# FMoto-Schematic.net
KiCad netlist of a schematic drawn in EAGLE
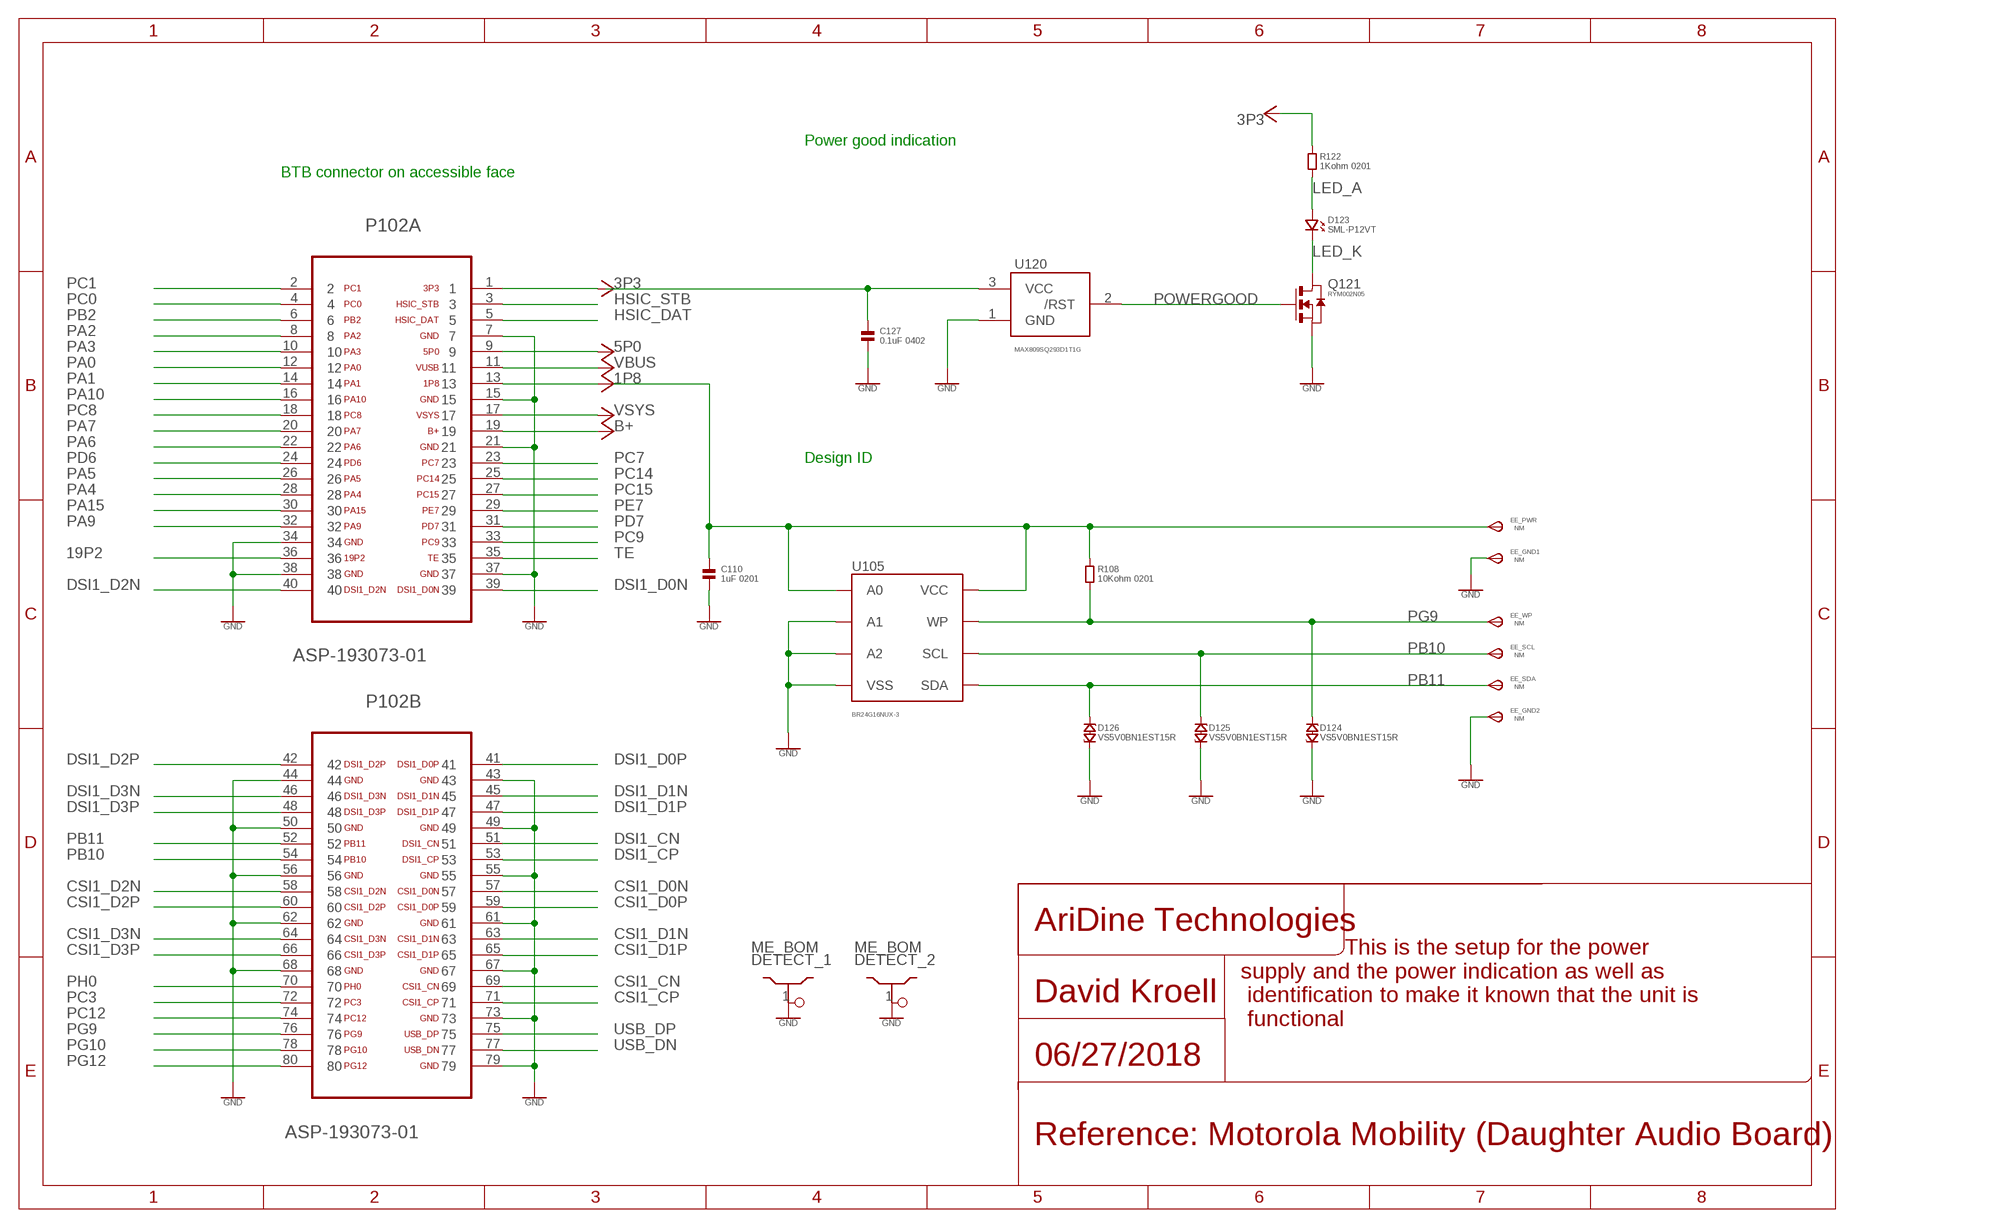
[diagram p0: schematic, sheet 1]
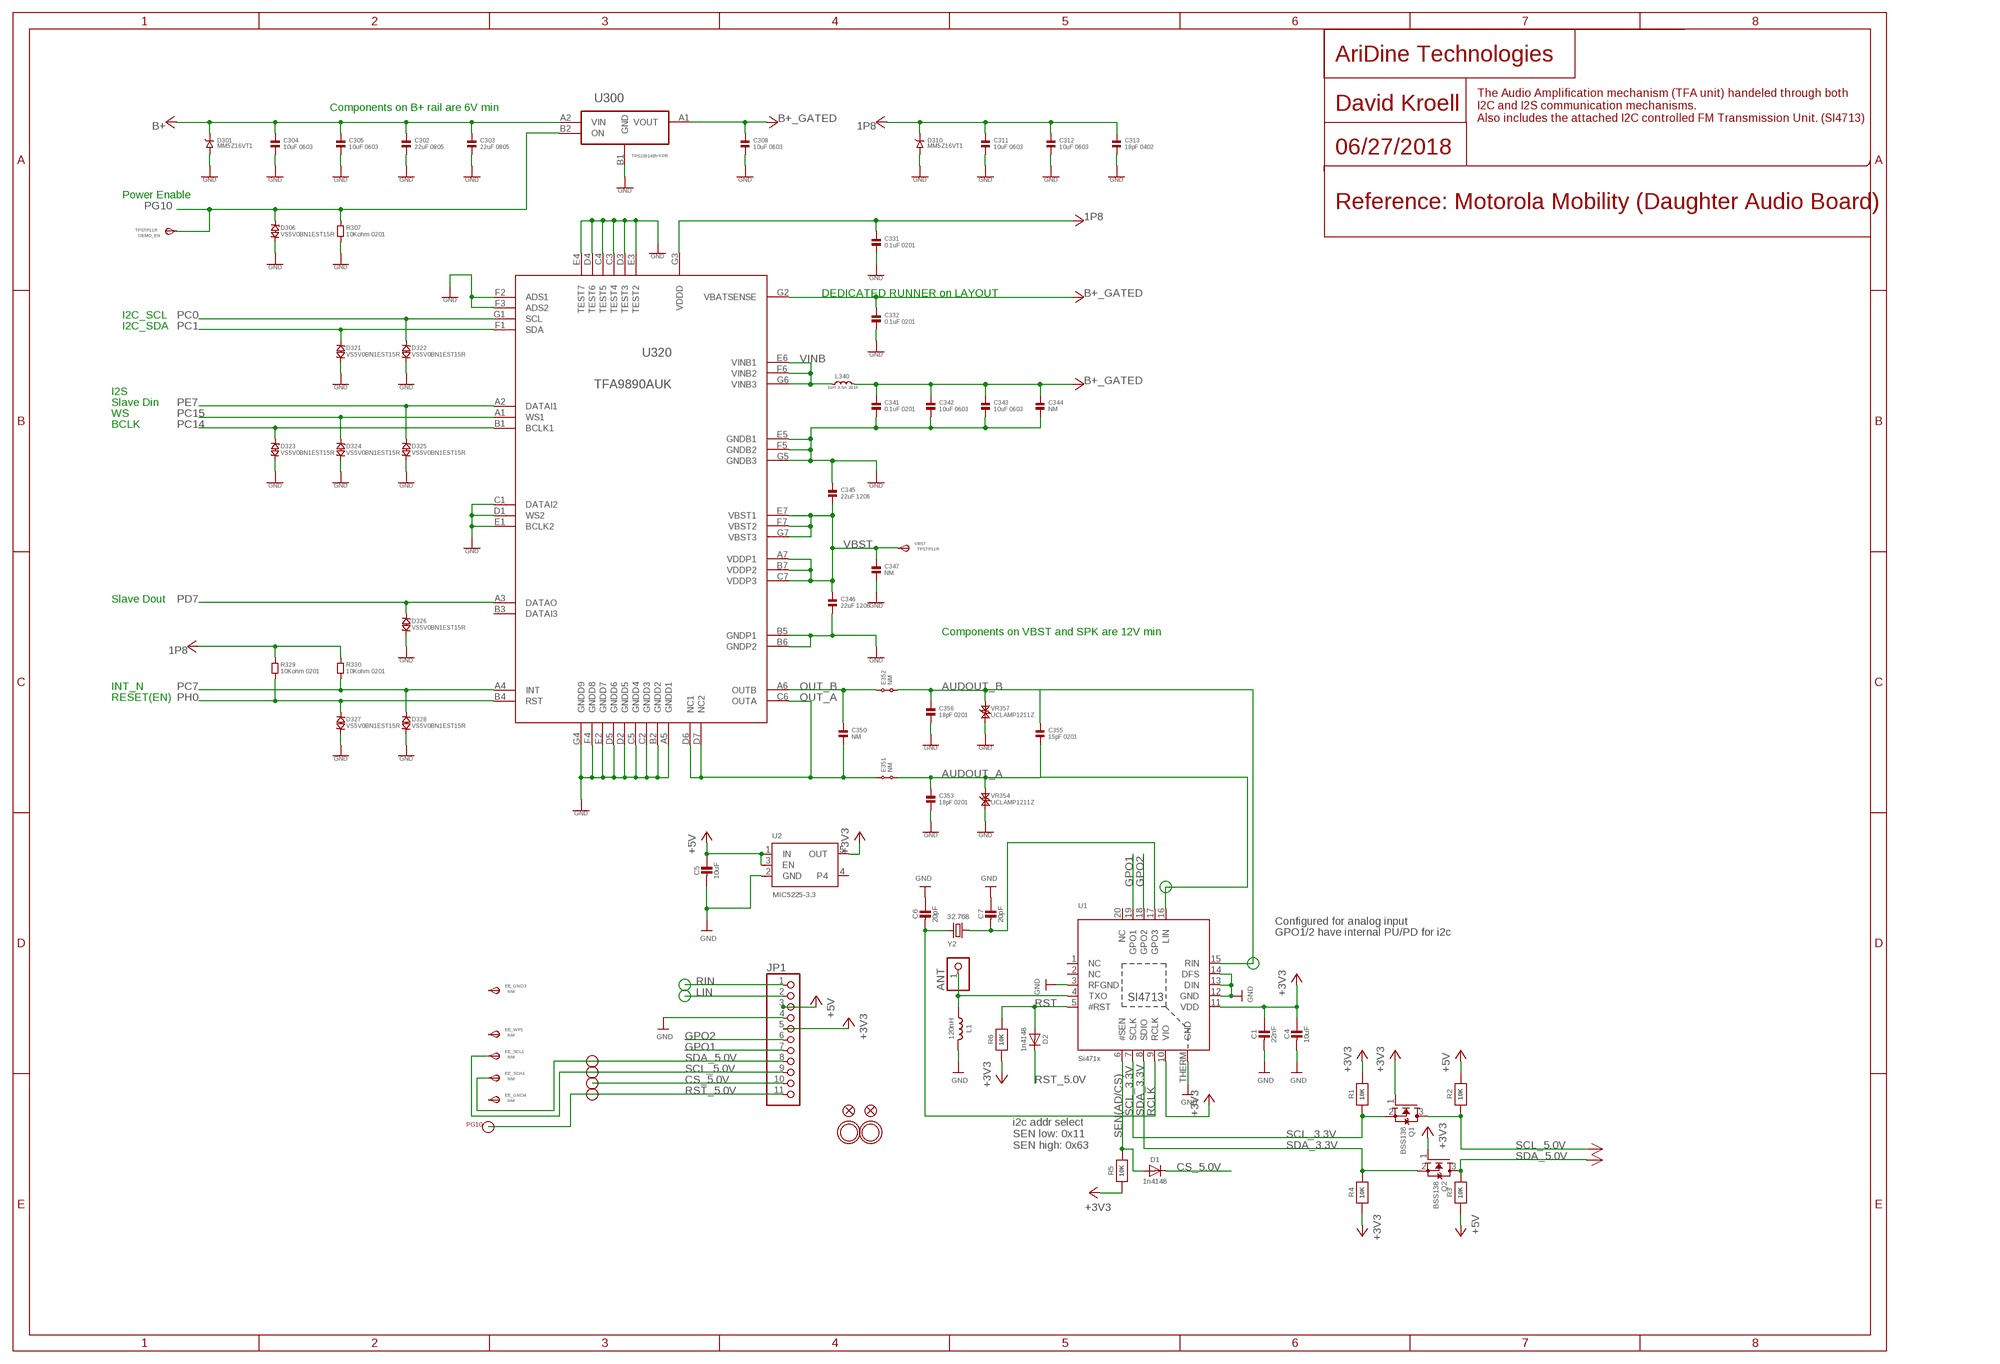
[diagram p1: schematic, sheet 2]

(export (version "E")
  (design (tool "Eeschema 10.0.6"))
  (components
    (comp (ref "ANT")
      (value "PINHD-1X1")
      (footprint "eagle-import:1X01")
      (libsource (lib "eagle-import") (part "PINHD-1X1"))
    )
    (comp (ref "C1")
      (value "22nF")
      (footprint "eagle-import:0805-NO")
      (libsource (lib "eagle-import") (part "CAP_CERAMIC0805-NOOUTLINE"))
    )
    (comp (ref "C4")
      (value "10uF")
      (footprint "eagle-import:0805-NO")
      (libsource (lib "eagle-import") (part "CAP_CERAMIC0805-NOOUTLINE"))
    )
    (comp (ref "C5")
      (value "10uF")
      (footprint "eagle-import:0805-NO")
      (libsource (lib "eagle-import") (part "CAP_CERAMIC0805-NOOUTLINE"))
    )
    (comp (ref "C6")
      (value "20pF")
      (footprint "eagle-import:0805-NO")
      (libsource (lib "eagle-import") (part "CAP_CERAMIC0805-NOOUTLINE"))
    )
    (comp (ref "C7")
      (value "20pF")
      (footprint "eagle-import:0805-NO")
      (libsource (lib "eagle-import") (part "CAP_CERAMIC0805-NOOUTLINE"))
    )
    (comp (ref "C302")
      (value "22uF 0805")
      (footprint "eagle-import:0805")
      (libsource (lib "eagle-import") (part "CAPACITOR.0805"))
    )
    (comp (ref "C303")
      (value "22uF 0805")
      (footprint "eagle-import:0805")
      (libsource (lib "eagle-import") (part "CAPACITOR.0805"))
    )
    (comp (ref "C304")
      (value "10uF 0603")
      (footprint "eagle-import:0603")
      (libsource (lib "eagle-import") (part "CAPACITOR.0603"))
    )
    (comp (ref "C305")
      (value "10uF 0603")
      (footprint "eagle-import:0603")
      (libsource (lib "eagle-import") (part "CAPACITOR.0603"))
    )
    (comp (ref "C308")
      (value "10uF 0603")
      (footprint "eagle-import:0603")
      (libsource (lib "eagle-import") (part "CAPACITOR.0603"))
    )
    (comp (ref "C311")
      (value "10uF 0603")
      (footprint "eagle-import:0603")
      (libsource (lib "eagle-import") (part "CAPACITOR.0603"))
    )
    (comp (ref "C312")
      (value "10uF 0603")
      (footprint "eagle-import:0603")
      (libsource (lib "eagle-import") (part "CAPACITOR.0603"))
    )
    (comp (ref "C313")
      (value "18pF 0402")
      (footprint "eagle-import:0402")
      (libsource (lib "eagle-import") (part "CAPACITOR.0402"))
    )
    (comp (ref "C331")
      (value "0.1uF 0201")
      (footprint "eagle-import:0201")
      (libsource (lib "eagle-import") (part "CAPACITOR.0201"))
    )
    (comp (ref "C332")
      (value "0.1uF 0201")
      (footprint "eagle-import:0201")
      (libsource (lib "eagle-import") (part "CAPACITOR.0201"))
    )
    (comp (ref "C341")
      (value "0.1uF 0201")
      (footprint "eagle-import:0201")
      (libsource (lib "eagle-import") (part "CAPACITOR.0201"))
    )
    (comp (ref "C342")
      (value "10uF 0603")
      (footprint "eagle-import:0603")
      (libsource (lib "eagle-import") (part "CAPACITOR.0603"))
    )
    (comp (ref "C343")
      (value "10uF 0603")
      (footprint "eagle-import:0603")
      (libsource (lib "eagle-import") (part "CAPACITOR.0603"))
    )
    (comp (ref "C344")
      (value "NM")
      (footprint "eagle-import:0402")
      (libsource (lib "eagle-import") (part "CAPACITOR.0402"))
    )
    (comp (ref "C345")
      (value "22uF 1206")
      (footprint "eagle-import:1206")
      (libsource (lib "eagle-import") (part "CAPACITOR.1206"))
    )
    (comp (ref "C346")
      (value "22uF 1206")
      (footprint "eagle-import:1206")
      (libsource (lib "eagle-import") (part "CAPACITOR.1206"))
    )
    (comp (ref "C347")
      (value "NM")
      (footprint "eagle-import:0402")
      (libsource (lib "eagle-import") (part "CAPACITOR.0402"))
    )
    (comp (ref "C350")
      (value "NM")
      (footprint "eagle-import:0201")
      (libsource (lib "eagle-import") (part "CAPACITOR.0201"))
    )
    (comp (ref "C353")
      (value "18pF 0201")
      (footprint "eagle-import:0201")
      (libsource (lib "eagle-import") (part "CAPACITOR.0201"))
    )
    (comp (ref "C355")
      (value "15pF 0201")
      (footprint "eagle-import:0201")
      (libsource (lib "eagle-import") (part "CAPACITOR.0201"))
    )
    (comp (ref "C356")
      (value "18pF 0201")
      (footprint "eagle-import:0201")
      (libsource (lib "eagle-import") (part "CAPACITOR.0201"))
    )
    (comp (ref "D1")
      (value "1n4148")
      (footprint "eagle-import:SOD-323")
      (libsource (lib "eagle-import") (part "DIODESOD-323"))
    )
    (comp (ref "D2")
      (value "1n4148")
      (footprint "eagle-import:SOD-323")
      (libsource (lib "eagle-import") (part "DIODESOD-323"))
    )
    (comp (ref "D301")
      (value "MM5Z16VT1")
      (footprint "eagle-import:SOD523")
      (libsource (lib "eagle-import") (part "DIODE.SOD523"))
    )
    (comp (ref "D306")
      (value "VS5V0BN1EST15R")
      (footprint "eagle-import:CHIP_0201")
      (libsource (lib "eagle-import") (part "ESD_VARISTOR.0201"))
    )
    (comp (ref "D310")
      (value "MM5Z16VT1")
      (footprint "eagle-import:SOD523")
      (libsource (lib "eagle-import") (part "DIODE.SOD523"))
    )
    (comp (ref "D321")
      (value "VS5V0BN1EST15R")
      (footprint "eagle-import:CHIP_0201")
      (libsource (lib "eagle-import") (part "ESD_VARISTOR.0201"))
    )
    (comp (ref "D322")
      (value "VS5V0BN1EST15R")
      (footprint "eagle-import:CHIP_0201")
      (libsource (lib "eagle-import") (part "ESD_VARISTOR.0201"))
    )
    (comp (ref "D323")
      (value "VS5V0BN1EST15R")
      (footprint "eagle-import:CHIP_0201")
      (libsource (lib "eagle-import") (part "ESD_VARISTOR.0201"))
    )
    (comp (ref "D324")
      (value "VS5V0BN1EST15R")
      (footprint "eagle-import:CHIP_0201")
      (libsource (lib "eagle-import") (part "ESD_VARISTOR.0201"))
    )
    (comp (ref "D325")
      (value "VS5V0BN1EST15R")
      (footprint "eagle-import:CHIP_0201")
      (libsource (lib "eagle-import") (part "ESD_VARISTOR.0201"))
    )
    (comp (ref "D326")
      (value "VS5V0BN1EST15R")
      (footprint "eagle-import:CHIP_0201")
      (libsource (lib "eagle-import") (part "ESD_VARISTOR.0201"))
    )
    (comp (ref "D327")
      (value "VS5V0BN1EST15R")
      (footprint "eagle-import:CHIP_0201")
      (libsource (lib "eagle-import") (part "ESD_VARISTOR.0201"))
    )
    (comp (ref "D328")
      (value "VS5V0BN1EST15R")
      (footprint "eagle-import:CHIP_0201")
      (libsource (lib "eagle-import") (part "ESD_VARISTOR.0201"))
    )
    (comp (ref "DEMO_EN")
      (value "TPSTP11R")
      (footprint "eagle-import:TP11R")
      (libsource (lib "eagle-import") (part "TPSTP11R"))
    )
    (comp (ref "E351")
      (value "NM")
      (footprint "eagle-import:0603_SHORT")
      (libsource (lib "eagle-import") (part "SHORT_BAR.0603"))
    )
    (comp (ref "E352")
      (value "NM")
      (footprint "eagle-import:0603_SHORT")
      (libsource (lib "eagle-import") (part "SHORT_BAR.0603"))
    )
    (comp (ref "EE_GND3")
      (value "NM")
      (footprint "eagle-import:TP11R")
      (libsource (lib "eagle-import") (part "TPSTP11R"))
    )
    (comp (ref "EE_GND4")
      (value "NM")
      (footprint "eagle-import:TP11R")
      (libsource (lib "eagle-import") (part "TPSTP11R"))
    )
    (comp (ref "EE_SCL1")
      (value "NM")
      (footprint "eagle-import:TP11R")
      (libsource (lib "eagle-import") (part "TPSTP11R"))
    )
    (comp (ref "EE_SDA1")
      (value "NM")
      (footprint "eagle-import:TP11R")
      (libsource (lib "eagle-import") (part "TPSTP11R"))
    )
    (comp (ref "EE_WP1")
      (value "NM")
      (footprint "eagle-import:TP11R")
      (libsource (lib "eagle-import") (part "TPSTP11R"))
    )
    (comp (ref "FID1")
      (value "FIDUCIAL\"\"")
      (footprint "eagle-import:FIDUCIAL_1MM")
      (libsource (lib "eagle-import") (part "FIDUCIAL{dblquote}{dblquote}"))
    )
    (comp (ref "FID2")
      (value "FIDUCIAL\"\"")
      (footprint "eagle-import:FIDUCIAL_1MM")
      (libsource (lib "eagle-import") (part "FIDUCIAL{dblquote}{dblquote}"))
    )
    (comp (ref "JP1")
      (value "HEADER-1X11")
      (footprint "eagle-import:1X11_ROUND")
      (libsource (lib "eagle-import") (part "HEADER-1X11"))
    )
    (comp (ref "L1")
      (value "120nH")
      (footprint "eagle-import:_0805")
      (libsource (lib "eagle-import") (part "INDUCTOR_0805"))
    )
    (comp (ref "L340")
      (value "1uH 3.5A 2016")
      (footprint "eagle-import:2016")
      (libsource (lib "eagle-import") (part "POWER-INDUCTOR.2016"))
    )
    (comp (ref "Q1")
      (value "BSS138")
      (footprint "eagle-import:SOT23")
      (libsource (lib "eagle-import") (part "MOSFET-NREFLOW"))
    )
    (comp (ref "Q2")
      (value "BSS138")
      (footprint "eagle-import:SOT23")
      (libsource (lib "eagle-import") (part "MOSFET-NREFLOW"))
    )
    (comp (ref "R1")
      (value "10K")
      (footprint "eagle-import:0805-NO")
      (libsource (lib "eagle-import") (part "RESISTOR0805_NOOUTLINE"))
    )
    (comp (ref "R2")
      (value "10K")
      (footprint "eagle-import:_0805MP")
      (libsource (lib "eagle-import") (part "RESISTOR_0805MP"))
    )
    (comp (ref "R3")
      (value "10K")
      (footprint "eagle-import:0805-NO")
      (libsource (lib "eagle-import") (part "RESISTOR0805_NOOUTLINE"))
    )
    (comp (ref "R4")
      (value "10K")
      (footprint "eagle-import:_0805MP")
      (libsource (lib "eagle-import") (part "RESISTOR_0805MP"))
    )
    (comp (ref "R5")
      (value "10K")
      (footprint "eagle-import:0805-NO")
      (libsource (lib "eagle-import") (part "RESISTOR0805_NOOUTLINE"))
    )
    (comp (ref "R6")
      (value "10K")
      (footprint "eagle-import:0805-NO")
      (libsource (lib "eagle-import") (part "RESISTOR0805_NOOUTLINE"))
    )
    (comp (ref "R307")
      (value "10Kohm 0201")
      (footprint "eagle-import:0201")
      (libsource (lib "eagle-import") (part "RESISTOR.0201"))
    )
    (comp (ref "R329")
      (value "10Kohm 0201")
      (footprint "eagle-import:0201")
      (libsource (lib "eagle-import") (part "RESISTOR.0201"))
    )
    (comp (ref "R330")
      (value "10Kohm 0201")
      (footprint "eagle-import:0201")
      (libsource (lib "eagle-import") (part "RESISTOR.0201"))
    )
    (comp (ref "U$15")
      (value "MOUNTINGHOLE2.5")
      (footprint "eagle-import:MOUNTINGHOLE_2.5_PLATED")
      (libsource (lib "eagle-import") (part "MOUNTINGHOLE2.5"))
    )
    (comp (ref "U$17")
      (value "MOUNTINGHOLE2.5")
      (footprint "eagle-import:MOUNTINGHOLE_2.5_PLATED")
      (libsource (lib "eagle-import") (part "MOUNTINGHOLE2.5"))
    )
    (comp (ref "U1")
      (value "Si471x")
      (footprint "eagle-import:SI471X")
      (libsource (lib "eagle-import") (part "SI471X"))
    )
    (comp (ref "U2")
      (value "MIC5225-3.3")
      (footprint "eagle-import:SOT23-5")
      (libsource (lib "eagle-import") (part "VREG_SOT23-5"))
    )
    (comp (ref "U300")
      (value "TPS22914BYFPR")
      (footprint "eagle-import:BGA0_75SQ_PS0_4_P4")
      (libsource (lib "eagle-import") (part "TPS22914BYFPR"))
    )
    (comp (ref "U320")
      (value "TFA9890AUK")
      (footprint "eagle-import:BGA7X7")
      (libsource (lib "eagle-import") (part "TFA9890AUK"))
    )
    (comp (ref "VBST")
      (value "TPSTP11R")
      (footprint "eagle-import:TP11R")
      (libsource (lib "eagle-import") (part "TPSTP11R"))
    )
    (comp (ref "VR354")
      (value "UCLAMP1211Z")
      (footprint "eagle-import:CHIP_0201")
      (libsource (lib "eagle-import") (part "ESD_TVS.0201"))
    )
    (comp (ref "VR357")
      (value "UCLAMP1211Z")
      (footprint "eagle-import:CHIP_0201")
      (libsource (lib "eagle-import") (part "ESD_TVS.0201"))
    )
    (comp (ref "Y2")
      (value "32.768")
      (footprint "eagle-import:CRYSTAL_8X3.8")
      (libsource (lib "eagle-import") (part "CRYSTAL8.0X3.8"))
    )
    (comp (ref "C110")
      (value "1uF 0201")
      (footprint "eagle-import:0201")
      (libsource (lib "eagle-import") (part "CAPACITOR.0201"))
    )
    (comp (ref "C127")
      (value "0.1uF 0402")
      (footprint "eagle-import:0402")
      (libsource (lib "eagle-import") (part "CAPACITOR.0402"))
    )
    (comp (ref "D123")
      (value "SML-P12VT")
      (footprint "eagle-import:0503.LED")
      (libsource (lib "eagle-import") (part "LED.0503"))
    )
    (comp (ref "D124")
      (value "VS5V0BN1EST15R")
      (footprint "eagle-import:CHIP_0201")
      (libsource (lib "eagle-import") (part "ESD_VARISTOR.0201"))
    )
    (comp (ref "D125")
      (value "VS5V0BN1EST15R")
      (footprint "eagle-import:CHIP_0201")
      (libsource (lib "eagle-import") (part "ESD_VARISTOR.0201"))
    )
    (comp (ref "D126")
      (value "VS5V0BN1EST15R")
      (footprint "eagle-import:CHIP_0201")
      (libsource (lib "eagle-import") (part "ESD_VARISTOR.0201"))
    )
    (comp (ref "DETECT_1")
      (value "ME_BOM")
      (footprint "eagle-import:PLUG")
      (fields (field (name "MPN") "refer to ME BOM"))
      (libsource (lib "eagle-import") (part "SHIELDDETECT"))
    )
    (comp (ref "DETECT_2")
      (value "ME_BOM")
      (footprint "eagle-import:PLUG")
      (fields (field (name "MPN") "refer to ME BOM"))
      (libsource (lib "eagle-import") (part "SHIELDDETECT"))
    )
    (comp (ref "EE_GND1")
      (value "NM")
      (footprint "eagle-import:TP11R")
      (libsource (lib "eagle-import") (part "TPSTP11R"))
    )
    (comp (ref "EE_GND2")
      (value "NM")
      (footprint "eagle-import:TP11R")
      (libsource (lib "eagle-import") (part "TPSTP11R"))
    )
    (comp (ref "EE_PWR")
      (value "NM")
      (footprint "eagle-import:TP11R")
      (libsource (lib "eagle-import") (part "TPSTP11R"))
    )
    (comp (ref "EE_SCL")
      (value "NM")
      (footprint "eagle-import:TP11R")
      (libsource (lib "eagle-import") (part "TPSTP11R"))
    )
    (comp (ref "EE_SDA")
      (value "NM")
      (footprint "eagle-import:TP11R")
      (libsource (lib "eagle-import") (part "TPSTP11R"))
    )
    (comp (ref "EE_WP")
      (value "NM")
      (footprint "eagle-import:TP11R")
      (libsource (lib "eagle-import") (part "TPSTP11R"))
    )
    (comp (ref "P102")
      (value "ASP-193073-01")
      (footprint "eagle-import:FTMH-140-02-L-DV-ES-P-TR")
      (fields (field (name "MPN") "ASP-193073-01"))
      (libsource (lib "eagle-import") (part "FTMH-140-02-L-DV-ES-P-TR"))
    )
    (comp (ref "Q121")
      (value "RYM002N05")
      (footprint "eagle-import:VMT3")
      (libsource (lib "eagle-import") (part "FET-NRYM002N05"))
    )
    (comp (ref "R108")
      (value "10Kohm 0201")
      (footprint "eagle-import:0201")
      (libsource (lib "eagle-import") (part "RESISTOR.0201"))
    )
    (comp (ref "R122")
      (value "1Kohm 0201")
      (footprint "eagle-import:0201")
      (libsource (lib "eagle-import") (part "RESISTOR.0201"))
    )
    (comp (ref "U105")
      (value "BR24G16NUX-3")
      (footprint "eagle-import:DFN-8")
      (libsource (lib "eagle-import") (part "EEPROMDFN8"))
    )
    (comp (ref "U120")
      (value "MAX809SQ293D1T1G")
      (footprint "eagle-import:SC70-3L")
      (fields (field (name "MPN") "MAX809SQ293D1T1"))
      (libsource (lib "eagle-import") (part "MAX809"))
    )
  )
  (nets
    (net (code "1") (name "+3V3") (class "Default")
      (node (ref "C1") (pin "1") (pinfunction "1_1") (pintype "passive"))
      (node (ref "C4") (pin "1") (pinfunction "1_1") (pintype "passive"))
      (node (ref "JP1") (pin "5") (pinfunction "5_5") (pintype "passive"))
      (node (ref "Q1") (pin "1") (pinfunction "G_1") (pintype "bidirectional"))
      (node (ref "Q2") (pin "1") (pinfunction "G_1") (pintype "bidirectional"))
      (node (ref "R1") (pin "2") (pinfunction "2_2") (pintype "passive"))
      (node (ref "R4") (pin "1") (pinfunction "1_1") (pintype "passive"))
      (node (ref "R5") (pin "1") (pinfunction "1_1") (pintype "passive"))
      (node (ref "R6") (pin "1") (pinfunction "1_1") (pintype "passive"))
      (node (ref "U1") (pin "10") (pinfunction "VIO_10") (pintype "bidirectional"))
      (node (ref "U1") (pin "11") (pinfunction "VDD_11") (pintype "bidirectional"))
      (node (ref "U2") (pin "5") (pinfunction "OUT_5") (pintype "power_in"))
    )
    (net (code "2") (name "+5V") (class "Default")
      (node (ref "C5") (pin "1") (pinfunction "1_1") (pintype "passive"))
      (node (ref "JP1") (pin "3") (pinfunction "3_3") (pintype "passive"))
      (node (ref "R2") (pin "2") (pinfunction "2_2") (pintype "passive"))
      (node (ref "R3") (pin "1") (pinfunction "1_1") (pintype "passive"))
      (node (ref "U2") (pin "1") (pinfunction "IN_1") (pintype "power_in"))
      (node (ref "U2") (pin "3") (pinfunction "EN_3") (pintype "input"))
    )
    (net (code "3") (name "1P8") (class "Default")
      (node (ref "C311") (pin "1") (pinfunction "1_1") (pintype "bidirectional"))
      (node (ref "C312") (pin "1") (pinfunction "1_1") (pintype "bidirectional"))
      (node (ref "C313") (pin "1") (pinfunction "1_1") (pintype "bidirectional"))
      (node (ref "C331") (pin "1") (pinfunction "1_1") (pintype "bidirectional"))
      (node (ref "D310") (pin "1") (pinfunction "1_1") (pintype "bidirectional"))
      (node (ref "P102") (pin "13") (pinfunction "13_13") (pintype "passive"))
      (node (ref "R329") (pin "1") (pinfunction "1_1") (pintype "bidirectional"))
      (node (ref "R330") (pin "1") (pinfunction "1_1") (pintype "bidirectional"))
      (node (ref "U320") (pin "G3") (pinfunction "VDDD_G3") (pintype "bidirectional"))
    )
    (net (code "4") (name "3P3") (class "Default")
      (node (ref "P102") (pin "1") (pinfunction "1_1") (pintype "passive"))
      (node (ref "R122") (pin "1") (pinfunction "1_1") (pintype "bidirectional"))
    )
    (net (code "5") (name "5P0") (class "Default")
      (node (ref "P102") (pin "9") (pinfunction "9_9") (pintype "passive"))
    )
    (net (code "6") (name "19P2") (class "Default")
      (node (ref "P102") (pin "36") (pinfunction "36_36") (pintype "passive"))
    )
    (net (code "7") (name "AUDOUT_A") (class "Default")
      (node (ref "C353") (pin "1") (pinfunction "1_1") (pintype "bidirectional"))
      (node (ref "C355") (pin "2") (pinfunction "2_2") (pintype "bidirectional"))
      (node (ref "E351") (pin "2") (pinfunction "2_2") (pintype "bidirectional"))
      (node (ref "U1") (pin "16") (pinfunction "LIN_16") (pintype "bidirectional"))
      (node (ref "VR354") (pin "P$1") (pinfunction "1_P$1") (pintype "bidirectional"))
    )
    (net (code "8") (name "AUDOUT_B") (class "Default")
      (node (ref "C355") (pin "1") (pinfunction "1_1") (pintype "bidirectional"))
      (node (ref "C356") (pin "1") (pinfunction "1_1") (pintype "bidirectional"))
      (node (ref "E352") (pin "2") (pinfunction "2_2") (pintype "bidirectional"))
      (node (ref "U1") (pin "15") (pinfunction "RIN_15") (pintype "bidirectional"))
      (node (ref "VR357") (pin "P$1") (pinfunction "1_P$1") (pintype "bidirectional"))
    )
    (net (code "9") (name "B+") (class "Default")
      (node (ref "C302") (pin "1") (pinfunction "1_1") (pintype "bidirectional"))
      (node (ref "C303") (pin "1") (pinfunction "1_1") (pintype "bidirectional"))
      (node (ref "C304") (pin "1") (pinfunction "1_1") (pintype "bidirectional"))
      (node (ref "C305") (pin "1") (pinfunction "1_1") (pintype "bidirectional"))
      (node (ref "D301") (pin "1") (pinfunction "1_1") (pintype "bidirectional"))
      (node (ref "P102") (pin "19") (pinfunction "19_19") (pintype "passive"))
      (node (ref "U300") (pin "A2") (pinfunction "VIN_A2") (pintype "power_in"))
    )
    (net (code "10") (name "B+_GATED") (class "Default")
      (node (ref "C308") (pin "1") (pinfunction "1_1") (pintype "bidirectional"))
      (node (ref "C332") (pin "1") (pinfunction "1_1") (pintype "bidirectional"))
      (node (ref "C341") (pin "1") (pinfunction "1_1") (pintype "bidirectional"))
      (node (ref "C342") (pin "1") (pinfunction "1_1") (pintype "bidirectional"))
      (node (ref "C343") (pin "1") (pinfunction "1_1") (pintype "bidirectional"))
      (node (ref "C344") (pin "1") (pinfunction "1_1") (pintype "bidirectional"))
      (node (ref "L340") (pin "2") (pinfunction "2_2") (pintype "passive"))
      (node (ref "U300") (pin "A1") (pinfunction "VOUT_A1") (pintype "power_in"))
      (node (ref "U320") (pin "G2") (pinfunction "VBATSENSE_G2") (pintype "bidirectional"))
    )
    (net (code "11") (name "CSI1_CN") (class "Default")
      (node (ref "P102") (pin "69") (pinfunction "69_69") (pintype "passive"))
    )
    (net (code "12") (name "CSI1_CP") (class "Default")
      (node (ref "P102") (pin "71") (pinfunction "71_71") (pintype "passive"))
    )
    (net (code "13") (name "CSI1_D0N") (class "Default")
      (node (ref "P102") (pin "57") (pinfunction "57_57") (pintype "passive"))
    )
    (net (code "14") (name "CSI1_D0P") (class "Default")
      (node (ref "P102") (pin "59") (pinfunction "59_59") (pintype "passive"))
    )
    (net (code "15") (name "CSI1_D1N") (class "Default")
      (node (ref "P102") (pin "63") (pinfunction "63_63") (pintype "passive"))
    )
    (net (code "16") (name "CSI1_D1P") (class "Default")
      (node (ref "P102") (pin "65") (pinfunction "65_65") (pintype "passive"))
    )
    (net (code "17") (name "CSI1_D2N") (class "Default")
      (node (ref "P102") (pin "58") (pinfunction "58_58") (pintype "passive"))
    )
    (net (code "18") (name "CSI1_D2P") (class "Default")
      (node (ref "P102") (pin "60") (pinfunction "60_60") (pintype "passive"))
    )
    (net (code "19") (name "CSI1_D3N") (class "Default")
      (node (ref "P102") (pin "64") (pinfunction "64_64") (pintype "passive"))
    )
    (net (code "20") (name "CSI1_D3P") (class "Default")
      (node (ref "P102") (pin "66") (pinfunction "66_66") (pintype "passive"))
    )
    (net (code "21") (name "CS_5.0V") (class "Default")
      (node (ref "D1") (pin "C") (pinfunction "C_C") (pintype "passive"))
      (node (ref "JP1") (pin "10") (pinfunction "10_10") (pintype "passive"))
    )
    (net (code "22") (name "DSI1_CN") (class "Default")
      (node (ref "P102") (pin "51") (pinfunction "51_51") (pintype "passive"))
    )
    (net (code "23") (name "DSI1_CP") (class "Default")
      (node (ref "P102") (pin "53") (pinfunction "53_53") (pintype "passive"))
    )
    (net (code "24") (name "DSI1_D0N") (class "Default")
      (node (ref "P102") (pin "39") (pinfunction "39_39") (pintype "passive"))
    )
    (net (code "25") (name "DSI1_D0P") (class "Default")
      (node (ref "P102") (pin "41") (pinfunction "41_41") (pintype "passive"))
    )
    (net (code "26") (name "DSI1_D1N") (class "Default")
      (node (ref "P102") (pin "45") (pinfunction "45_45") (pintype "passive"))
    )
    (net (code "27") (name "DSI1_D1P") (class "Default")
      (node (ref "P102") (pin "47") (pinfunction "47_47") (pintype "passive"))
    )
    (net (code "28") (name "DSI1_D2N") (class "Default")
      (node (ref "P102") (pin "40") (pinfunction "40_40") (pintype "passive"))
    )
    (net (code "29") (name "DSI1_D2P") (class "Default")
      (node (ref "P102") (pin "42") (pinfunction "42_42") (pintype "passive"))
    )
    (net (code "30") (name "DSI1_D3N") (class "Default")
      (node (ref "P102") (pin "46") (pinfunction "46_46") (pintype "passive"))
    )
    (net (code "31") (name "DSI1_D3P") (class "Default")
      (node (ref "P102") (pin "48") (pinfunction "48_48") (pintype "passive"))
    )
    (net (code "32") (name "GND") (class "Default")
      (node (ref "C1") (pin "2") (pinfunction "2_2") (pintype "passive"))
      (node (ref "C110") (pin "2") (pinfunction "2_2") (pintype "bidirectional"))
      (node (ref "C127") (pin "2") (pinfunction "2_2") (pintype "bidirectional"))
      (node (ref "C302") (pin "2") (pinfunction "2_2") (pintype "bidirectional"))
      (node (ref "C303") (pin "2") (pinfunction "2_2") (pintype "bidirectional"))
      (node (ref "C304") (pin "2") (pinfunction "2_2") (pintype "bidirectional"))
      (node (ref "C305") (pin "2") (pinfunction "2_2") (pintype "bidirectional"))
      (node (ref "C308") (pin "2") (pinfunction "2_2") (pintype "bidirectional"))
      (node (ref "C311") (pin "2") (pinfunction "2_2") (pintype "bidirectional"))
      (node (ref "C312") (pin "2") (pinfunction "2_2") (pintype "bidirectional"))
      (node (ref "C313") (pin "2") (pinfunction "2_2") (pintype "bidirectional"))
      (node (ref "C331") (pin "2") (pinfunction "2_2") (pintype "bidirectional"))
      (node (ref "C332") (pin "2") (pinfunction "2_2") (pintype "bidirectional"))
      (node (ref "C341") (pin "2") (pinfunction "2_2") (pintype "bidirectional"))
      (node (ref "C342") (pin "2") (pinfunction "2_2") (pintype "bidirectional"))
      (node (ref "C343") (pin "2") (pinfunction "2_2") (pintype "bidirectional"))
      (node (ref "C344") (pin "2") (pinfunction "2_2") (pintype "bidirectional"))
      (node (ref "C345") (pin "1") (pinfunction "1_1") (pintype "bidirectional"))
      (node (ref "C346") (pin "2") (pinfunction "2_2") (pintype "bidirectional"))
      (node (ref "C347") (pin "2") (pinfunction "2_2") (pintype "bidirectional"))
      (node (ref "C353") (pin "2") (pinfunction "2_2") (pintype "bidirectional"))
      (node (ref "C356") (pin "2") (pinfunction "2_2") (pintype "bidirectional"))
      (node (ref "C4") (pin "2") (pinfunction "2_2") (pintype "passive"))
      (node (ref "C5") (pin "2") (pinfunction "2_2") (pintype "passive"))
      (node (ref "C6") (pin "1") (pinfunction "1_1") (pintype "passive"))
      (node (ref "C7") (pin "1") (pinfunction "1_1") (pintype "passive"))
      (node (ref "D124") (pin "P$2") (pinfunction "2_P$2") (pintype "bidirectional"))
      (node (ref "D125") (pin "P$2") (pinfunction "2_P$2") (pintype "bidirectional"))
      (node (ref "D126") (pin "P$2") (pinfunction "2_P$2") (pintype "bidirectional"))
      (node (ref "D301") (pin "2") (pinfunction "2_2") (pintype "bidirectional"))
      (node (ref "D306") (pin "P$2") (pinfunction "2_P$2") (pintype "bidirectional"))
      (node (ref "D310") (pin "2") (pinfunction "2_2") (pintype "bidirectional"))
      (node (ref "D321") (pin "P$2") (pinfunction "2_P$2") (pintype "bidirectional"))
      (node (ref "D322") (pin "P$2") (pinfunction "2_P$2") (pintype "bidirectional"))
      (node (ref "D323") (pin "P$2") (pinfunction "2_P$2") (pintype "bidirectional"))
      (node (ref "D324") (pin "P$2") (pinfunction "2_P$2") (pintype "bidirectional"))
      (node (ref "D325") (pin "P$2") (pinfunction "2_P$2") (pintype "bidirectional"))
      (node (ref "D326") (pin "P$2") (pinfunction "2_P$2") (pintype "bidirectional"))
      (node (ref "D327") (pin "P$2") (pinfunction "2_P$2") (pintype "bidirectional"))
      (node (ref "D328") (pin "P$2") (pinfunction "2_P$2") (pintype "bidirectional"))
      (node (ref "DETECT_1") (pin "1") (pinfunction "1_1") (pintype "passive"))
      (node (ref "DETECT_2") (pin "1") (pinfunction "1_1") (pintype "passive"))
      (node (ref "EE_GND1") (pin "TP") (pinfunction "PP_TP") (pintype "input"))
      (node (ref "EE_GND2") (pin "TP") (pinfunction "PP_TP") (pintype "input"))
      (node (ref "JP1") (pin "4") (pinfunction "4_4") (pintype "passive"))
      (node (ref "L1") (pin "2") (pinfunction "2_2") (pintype "passive"))
      (node (ref "P102") (pin "15") (pinfunction "15_15") (pintype "passive"))
      (node (ref "P102") (pin "21") (pinfunction "21_21") (pintype "passive"))
      (node (ref "P102") (pin "34") (pinfunction "34_34") (pintype "passive"))
      (node (ref "P102") (pin "37") (pinfunction "37_37") (pintype "passive"))
      (node (ref "P102") (pin "38") (pinfunction "38_38") (pintype "passive"))
      (node (ref "P102") (pin "43") (pinfunction "43_43") (pintype "passive"))
      (node (ref "P102") (pin "44") (pinfunction "44_44") (pintype "passive"))
      (node (ref "P102") (pin "49") (pinfunction "49_49") (pintype "passive"))
      (node (ref "P102") (pin "50") (pinfunction "50_50") (pintype "passive"))
      (node (ref "P102") (pin "55") (pinfunction "55_55") (pintype "passive"))
      (node (ref "P102") (pin "56") (pinfunction "56_56") (pintype "passive"))
      (node (ref "P102") (pin "61") (pinfunction "61_61") (pintype "passive"))
      (node (ref "P102") (pin "62") (pinfunction "62_62") (pintype "passive"))
      (node (ref "P102") (pin "67") (pinfunction "67_67") (pintype "passive"))
      (node (ref "P102") (pin "68") (pinfunction "68_68") (pintype "passive"))
      (node (ref "P102") (pin "7") (pinfunction "7_7") (pintype "passive"))
      (node (ref "P102") (pin "73") (pinfunction "73_73") (pintype "passive"))
      (node (ref "P102") (pin "79") (pinfunction "79_79") (pintype "passive"))
      (node (ref "Q121") (pin "2") (pinfunction "S_2") (pintype "passive"))
      (node (ref "R307") (pin "2") (pinfunction "2_2") (pintype "bidirectional"))
      (node (ref "U1") (pin "12") (pinfunction "GND_12") (pintype "bidirectional"))
      (node (ref "U1") (pin "13") (pinfunction "DIN_13") (pintype "bidirectional"))
      (node (ref "U1") (pin "14") (pinfunction "DFS_14") (pintype "bidirectional"))
      (node (ref "U1") (pin "3") (pinfunction "RFGND_3") (pintype "bidirectional"))
      (node (ref "U1") (pin "THERM") (pinfunction "GND_THERM") (pintype "bidirectional"))
      (node (ref "U105") (pin "P$2") (pinfunction "A1_P$2") (pintype "input"))
      (node (ref "U105") (pin "P$3") (pinfunction "A2_P$3") (pintype "input"))
      (node (ref "U105") (pin "P$4") (pinfunction "VSS_P$4") (pintype "power_in"))
      (node (ref "U105") (pin "P$9") (pinfunction "VSS_P$9") (pintype "power_in"))
      (node (ref "U120") (pin "1") (pinfunction "GND_1") (pintype "power_in"))
      (node (ref "U2") (pin "2") (pinfunction "GND_2") (pintype "power_in"))
      (node (ref "U300") (pin "B1") (pinfunction "GND_B1") (pintype "power_in"))
      (node (ref "U320") (pin "A5") (pinfunction "GNDD1_A5") (pintype "bidirectional"))
      (node (ref "U320") (pin "B2") (pinfunction "GNDD2_B2") (pintype "bidirectional"))
      (node (ref "U320") (pin "B5") (pinfunction "GNDP1_B5") (pintype "bidirectional"))
      (node (ref "U320") (pin "B6") (pinfunction "GNDP2_B6") (pintype "bidirectional"))
      (node (ref "U320") (pin "C1") (pinfunction "DATAI2_C1") (pintype "bidirectional"))
      (node (ref "U320") (pin "C2") (pinfunction "GNDD3_C2") (pintype "bidirectional"))
      (node (ref "U320") (pin "C3") (pinfunction "TEST4_C3") (pintype "bidirectional"))
      (node (ref "U320") (pin "C4") (pinfunction "TEST5_C4") (pintype "bidirectional"))
      (node (ref "U320") (pin "C5") (pinfunction "GNDD4_C5") (pintype "bidirectional"))
      (node (ref "U320") (pin "D1") (pinfunction "WS2_D1") (pintype "bidirectional"))
      (node (ref "U320") (pin "D2") (pinfunction "GNDD5_D2") (pintype "bidirectional"))
      (node (ref "U320") (pin "D3") (pinfunction "TEST3_D3") (pintype "bidirectional"))
      (node (ref "U320") (pin "D4") (pinfunction "TEST6_D4") (pintype "bidirectional"))
      (node (ref "U320") (pin "D5") (pinfunction "GNDD6_D5") (pintype "bidirectional"))
      (node (ref "U320") (pin "E1") (pinfunction "BCLK2_E1") (pintype "bidirectional"))
      (node (ref "U320") (pin "E2") (pinfunction "GNDD7_E2") (pintype "bidirectional"))
      (node (ref "U320") (pin "E3") (pinfunction "TEST2_E3") (pintype "bidirectional"))
      (node (ref "U320") (pin "E4") (pinfunction "TEST7_E4") (pintype "bidirectional"))
      (node (ref "U320") (pin "E5") (pinfunction "GNDB1_E5") (pintype "bidirectional"))
      (node (ref "U320") (pin "F2") (pinfunction "ADS1_F2") (pintype "bidirectional"))
      (node (ref "U320") (pin "F3") (pinfunction "ADS2_F3") (pintype "bidirectional"))
      (node (ref "U320") (pin "F4") (pinfunction "GNDD8_F4") (pintype "bidirectional"))
      (node (ref "U320") (pin "F5") (pinfunction "GNDB2_F5") (pintype "bidirectional"))
      (node (ref "U320") (pin "G4") (pinfunction "GNDD9_G4") (pintype "bidirectional"))
      (node (ref "U320") (pin "G5") (pinfunction "GNDB3_G5") (pintype "bidirectional"))
      (node (ref "VR354") (pin "P$2") (pinfunction "2_P$2") (pintype "bidirectional"))
      (node (ref "VR357") (pin "P$2") (pinfunction "2_P$2") (pintype "bidirectional"))
    )
    (net (code "33") (name "GPO1") (class "Default")
      (node (ref "JP1") (pin "7") (pinfunction "7_7") (pintype "passive"))
      (node (ref "U1") (pin "19") (pinfunction "GPO1_19") (pintype "bidirectional"))
    )
    (net (code "34") (name "GPO2") (class "Default")
      (node (ref "JP1") (pin "6") (pinfunction "6_6") (pintype "passive"))
      (node (ref "U1") (pin "18") (pinfunction "GPO2_18") (pintype "bidirectional"))
    )
    (net (code "35") (name "HSIC_DAT") (class "Default")
      (node (ref "P102") (pin "5") (pinfunction "5_5") (pintype "passive"))
    )
    (net (code "36") (name "HSIC_STB") (class "Default")
      (node (ref "P102") (pin "3") (pinfunction "3_3") (pintype "passive"))
    )
    (net (code "37") (name "LED_A") (class "Default")
      (node (ref "D123") (pin "P$1") (pinfunction "1_P$1") (pintype "bidirectional"))
      (node (ref "R122") (pin "2") (pinfunction "2_2") (pintype "bidirectional"))
    )
    (net (code "38") (name "LED_K") (class "Default")
      (node (ref "D123") (pin "P$2") (pinfunction "2_P$2") (pintype "bidirectional"))
      (node (ref "Q121") (pin "3") (pinfunction "D_3") (pintype "passive"))
    )
    (net (code "39") (name "LIN") (class "Default")
      (node (ref "JP1") (pin "2") (pinfunction "2_2") (pintype "passive"))
    )
    (net (code "40") (name "Net-(EE_PWR-PP)") (class "Default")
      (node (ref "C110") (pin "1") (pinfunction "1_1") (pintype "bidirectional"))
      (node (ref "EE_PWR") (pin "TP") (pinfunction "PP_TP") (pintype "input"))
      (node (ref "R108") (pin "1") (pinfunction "1_1") (pintype "bidirectional"))
      (node (ref "U105") (pin "P$1") (pinfunction "A0_P$1") (pintype "input"))
      (node (ref "U105") (pin "P$8") (pinfunction "VCC_P$8") (pintype "power_in"))
    )
    (net (code "41") (name "Net-(U1-GPO3)") (class "Default")
      (node (ref "C7") (pin "2") (pinfunction "2_2") (pintype "passive"))
      (node (ref "U1") (pin "17") (pinfunction "GPO3_17") (pintype "bidirectional"))
      (node (ref "Y2") (pin "P$4") (pinfunction "2_P$4") (pintype "passive"))
    )
    (net (code "42") (name "Net-(U1-TXO)") (class "Default")
      (node (ref "ANT") (pin "1") (pinfunction "1_1") (pintype "passive"))
      (node (ref "L1") (pin "1") (pinfunction "1_1") (pintype "passive"))
      (node (ref "U1") (pin "4") (pinfunction "TXO_4") (pintype "bidirectional"))
    )
    (net (code "43") (name "Net-(U120-VCC)") (class "Default")
      (node (ref "C127") (pin "1") (pinfunction "1_1") (pintype "bidirectional"))
      (node (ref "U120") (pin "3") (pinfunction "VCC_3") (pintype "input"))
    )
    (net (code "44") (name "OUT_A") (class "Default")
      (node (ref "C350") (pin "2") (pinfunction "2_2") (pintype "bidirectional"))
      (node (ref "E351") (pin "1") (pinfunction "1_1") (pintype "bidirectional"))
      (node (ref "U320") (pin "C6") (pinfunction "OUTA_C6") (pintype "bidirectional"))
      (node (ref "U320") (pin "D6") (pinfunction "NC1_D6") (pintype "bidirectional"))
      (node (ref "U320") (pin "D7") (pinfunction "NC2_D7") (pintype "bidirectional"))
    )
    (net (code "45") (name "OUT_B") (class "Default")
      (node (ref "C350") (pin "1") (pinfunction "1_1") (pintype "bidirectional"))
      (node (ref "E352") (pin "1") (pinfunction "1_1") (pintype "bidirectional"))
      (node (ref "U320") (pin "A6") (pinfunction "OUTB_A6") (pintype "bidirectional"))
    )
    (net (code "46") (name "PA0") (class "Default")
      (node (ref "P102") (pin "12") (pinfunction "12_12") (pintype "passive"))
    )
    (net (code "47") (name "PA1") (class "Default")
      (node (ref "P102") (pin "14") (pinfunction "14_14") (pintype "passive"))
    )
    (net (code "48") (name "PA2") (class "Default")
      (node (ref "P102") (pin "8") (pinfunction "8_8") (pintype "passive"))
    )
    (net (code "49") (name "PA3") (class "Default")
      (node (ref "P102") (pin "10") (pinfunction "10_10") (pintype "passive"))
    )
    (net (code "50") (name "PA4") (class "Default")
      (node (ref "P102") (pin "28") (pinfunction "28_28") (pintype "passive"))
    )
    (net (code "51") (name "PA5") (class "Default")
      (node (ref "P102") (pin "26") (pinfunction "26_26") (pintype "passive"))
    )
    (net (code "52") (name "PA6") (class "Default")
      (node (ref "P102") (pin "22") (pinfunction "22_22") (pintype "passive"))
    )
    (net (code "53") (name "PA7") (class "Default")
      (node (ref "P102") (pin "20") (pinfunction "20_20") (pintype "passive"))
    )
    (net (code "54") (name "PA9") (class "Default")
      (node (ref "P102") (pin "32") (pinfunction "32_32") (pintype "passive"))
    )
    (net (code "55") (name "PA10") (class "Default")
      (node (ref "P102") (pin "16") (pinfunction "16_16") (pintype "passive"))
    )
    (net (code "56") (name "PA15") (class "Default")
      (node (ref "P102") (pin "30") (pinfunction "30_30") (pintype "passive"))
    )
    (net (code "57") (name "PB2") (class "Default")
      (node (ref "P102") (pin "6") (pinfunction "6_6") (pintype "passive"))
    )
    (net (code "58") (name "PB10") (class "Default")
      (node (ref "D125") (pin "P$1") (pinfunction "1_P$1") (pintype "bidirectional"))
      (node (ref "EE_SCL") (pin "TP") (pinfunction "PP_TP") (pintype "input"))
      (node (ref "P102") (pin "54") (pinfunction "54_54") (pintype "passive"))
      (node (ref "U105") (pin "P$6") (pinfunction "SCL_P$6") (pintype "input"))
    )
    (net (code "59") (name "PB11") (class "Default")
      (node (ref "D126") (pin "P$1") (pinfunction "1_P$1") (pintype "bidirectional"))
      (node (ref "EE_SDA") (pin "TP") (pinfunction "PP_TP") (pintype "input"))
      (node (ref "P102") (pin "52") (pinfunction "52_52") (pintype "passive"))
      (node (ref "U105") (pin "P$5") (pinfunction "SDA_P$5") (pintype "bidirectional"))
    )
    (net (code "60") (name "PC0") (class "Default")
      (node (ref "D322") (pin "P$1") (pinfunction "1_P$1") (pintype "bidirectional"))
      (node (ref "P102") (pin "4") (pinfunction "4_4") (pintype "passive"))
      (node (ref "U320") (pin "G1") (pinfunction "SCL_G1") (pintype "bidirectional"))
    )
    (net (code "61") (name "PC1") (class "Default")
      (node (ref "D321") (pin "P$1") (pinfunction "1_P$1") (pintype "bidirectional"))
      (node (ref "P102") (pin "2") (pinfunction "2_2") (pintype "passive"))
      (node (ref "U320") (pin "F1") (pinfunction "SDA_F1") (pintype "bidirectional"))
    )
    (net (code "62") (name "PC3") (class "Default")
      (node (ref "P102") (pin "72") (pinfunction "72_72") (pintype "passive"))
    )
    (net (code "63") (name "PC7") (class "Default")
      (node (ref "D328") (pin "P$1") (pinfunction "1_P$1") (pintype "bidirectional"))
      (node (ref "P102") (pin "23") (pinfunction "23_23") (pintype "passive"))
      (node (ref "R330") (pin "2") (pinfunction "2_2") (pintype "bidirectional"))
      (node (ref "U320") (pin "A4") (pinfunction "INT_A4") (pintype "bidirectional"))
    )
    (net (code "64") (name "PC8") (class "Default")
      (node (ref "P102") (pin "18") (pinfunction "18_18") (pintype "passive"))
    )
    (net (code "65") (name "PC9") (class "Default")
      (node (ref "P102") (pin "33") (pinfunction "33_33") (pintype "passive"))
    )
    (net (code "66") (name "PC12") (class "Default")
      (node (ref "P102") (pin "74") (pinfunction "74_74") (pintype "passive"))
    )
    (net (code "67") (name "PC14") (class "Default")
      (node (ref "D323") (pin "P$1") (pinfunction "1_P$1") (pintype "bidirectional"))
      (node (ref "P102") (pin "25") (pinfunction "25_25") (pintype "passive"))
      (node (ref "U320") (pin "B1") (pinfunction "BCLK1_B1") (pintype "bidirectional"))
    )
    (net (code "68") (name "PC15") (class "Default")
      (node (ref "D324") (pin "P$1") (pinfunction "1_P$1") (pintype "bidirectional"))
      (node (ref "P102") (pin "27") (pinfunction "27_27") (pintype "passive"))
      (node (ref "U320") (pin "A1") (pinfunction "WS1_A1") (pintype "bidirectional"))
    )
    (net (code "69") (name "PD6") (class "Default")
      (node (ref "P102") (pin "24") (pinfunction "24_24") (pintype "passive"))
    )
    (net (code "70") (name "PD7") (class "Default")
      (node (ref "D326") (pin "P$1") (pinfunction "1_P$1") (pintype "bidirectional"))
      (node (ref "P102") (pin "31") (pinfunction "31_31") (pintype "passive"))
      (node (ref "U320") (pin "A3") (pinfunction "DATAO_A3") (pintype "bidirectional"))
    )
    (net (code "71") (name "PE7") (class "Default")
      (node (ref "D325") (pin "P$1") (pinfunction "1_P$1") (pintype "bidirectional"))
      (node (ref "P102") (pin "29") (pinfunction "29_29") (pintype "passive"))
      (node (ref "U320") (pin "A2") (pinfunction "DATAI1_A2") (pintype "bidirectional"))
    )
    (net (code "72") (name "PG9") (class "Default")
      (node (ref "D124") (pin "P$1") (pinfunction "1_P$1") (pintype "bidirectional"))
      (node (ref "EE_WP") (pin "TP") (pinfunction "PP_TP") (pintype "input"))
      (node (ref "P102") (pin "76") (pinfunction "76_76") (pintype "passive"))
      (node (ref "R108") (pin "2") (pinfunction "2_2") (pintype "bidirectional"))
      (node (ref "U105") (pin "P$7") (pinfunction "WP_P$7") (pintype "input"))
    )
    (net (code "73") (name "PG10") (class "Default")
      (node (ref "D306") (pin "P$1") (pinfunction "1_P$1") (pintype "bidirectional"))
      (node (ref "DEMO_EN") (pin "TP") (pinfunction "PP_TP") (pintype "input"))
      (node (ref "P102") (pin "78") (pinfunction "78_78") (pintype "passive"))
      (node (ref "R307") (pin "1") (pinfunction "1_1") (pintype "bidirectional"))
      (node (ref "U300") (pin "B2") (pinfunction "ON_B2") (pintype "input"))
    )
    (net (code "74") (name "PG12") (class "Default")
      (node (ref "P102") (pin "80") (pinfunction "80_80") (pintype "passive"))
    )
    (net (code "75") (name "PH0") (class "Default")
      (node (ref "D327") (pin "P$1") (pinfunction "1_P$1") (pintype "bidirectional"))
      (node (ref "P102") (pin "70") (pinfunction "70_70") (pintype "passive"))
      (node (ref "R329") (pin "2") (pinfunction "2_2") (pintype "bidirectional"))
      (node (ref "U320") (pin "B4") (pinfunction "RST_B4") (pintype "bidirectional"))
    )
    (net (code "76") (name "POWERGOOD") (class "Default")
      (node (ref "Q121") (pin "1") (pinfunction "G_1") (pintype "passive"))
      (node (ref "U120") (pin "2") (pinfunction "/RST_2") (pintype "output"))
    )
    (net (code "77") (name "RCLK") (class "Default")
      (node (ref "C6") (pin "2") (pinfunction "2_2") (pintype "passive"))
      (node (ref "U1") (pin "9") (pinfunction "RCLK_9") (pintype "bidirectional"))
      (node (ref "Y2") (pin "P$1") (pinfunction "1_P$1") (pintype "passive"))
    )
    (net (code "78") (name "RIN") (class "Default")
      (node (ref "JP1") (pin "1") (pinfunction "1_1") (pintype "passive"))
    )
    (net (code "79") (name "RST") (class "Default")
      (node (ref "D2") (pin "A") (pinfunction "A_A") (pintype "passive"))
      (node (ref "R6") (pin "2") (pinfunction "2_2") (pintype "passive"))
      (node (ref "U1") (pin "5") (pinfunction "#RST_5") (pintype "bidirectional"))
    )
    (net (code "80") (name "RST_5.0V") (class "Default")
      (node (ref "D2") (pin "C") (pinfunction "C_C") (pintype "passive"))
      (node (ref "JP1") (pin "11") (pinfunction "11_11") (pintype "passive"))
    )
    (net (code "81") (name "SCL_3.3V") (class "Default")
      (node (ref "Q1") (pin "2") (pinfunction "S_2") (pintype "bidirectional"))
      (node (ref "R1") (pin "1") (pinfunction "1_1") (pintype "passive"))
      (node (ref "U1") (pin "7") (pinfunction "SCLK_7") (pintype "bidirectional"))
    )
    (net (code "82") (name "SCL_5.0V") (class "Default")
      (node (ref "EE_SCL1") (pin "TP") (pinfunction "PP_TP") (pintype "input"))
      (node (ref "JP1") (pin "9") (pinfunction "9_9") (pintype "passive"))
      (node (ref "Q1") (pin "3") (pinfunction "D_3") (pintype "bidirectional"))
      (node (ref "R2") (pin "1") (pinfunction "1_1") (pintype "passive"))
    )
    (net (code "83") (name "SDA_3.3V") (class "Default")
      (node (ref "Q2") (pin "2") (pinfunction "S_2") (pintype "bidirectional"))
      (node (ref "R4") (pin "2") (pinfunction "2_2") (pintype "passive"))
      (node (ref "U1") (pin "8") (pinfunction "SDIO_8") (pintype "bidirectional"))
    )
    (net (code "84") (name "SDA_5.0V") (class "Default")
      (node (ref "EE_SDA1") (pin "TP") (pinfunction "PP_TP") (pintype "input"))
      (node (ref "JP1") (pin "8") (pinfunction "8_8") (pintype "passive"))
      (node (ref "Q2") (pin "3") (pinfunction "D_3") (pintype "bidirectional"))
      (node (ref "R3") (pin "2") (pinfunction "2_2") (pintype "passive"))
    )
    (net (code "85") (name "SEN(AD{slash}CS)") (class "Default")
      (node (ref "D1") (pin "A") (pinfunction "A_A") (pintype "passive"))
      (node (ref "R5") (pin "2") (pinfunction "2_2") (pintype "passive"))
      (node (ref "U1") (pin "6") (pinfunction "#SEN_6") (pintype "bidirectional"))
    )
    (net (code "86") (name "TE") (class "Default")
      (node (ref "P102") (pin "35") (pinfunction "35_35") (pintype "passive"))
    )
    (net (code "87") (name "USB_DN") (class "Default")
      (node (ref "P102") (pin "77") (pinfunction "77_77") (pintype "passive"))
    )
    (net (code "88") (name "USB_DP") (class "Default")
      (node (ref "P102") (pin "75") (pinfunction "75_75") (pintype "passive"))
    )
    (net (code "89") (name "VBST") (class "Default")
      (node (ref "C345") (pin "2") (pinfunction "2_2") (pintype "bidirectional"))
      (node (ref "C346") (pin "1") (pinfunction "1_1") (pintype "bidirectional"))
      (node (ref "C347") (pin "1") (pinfunction "1_1") (pintype "bidirectional"))
      (node (ref "U320") (pin "A7") (pinfunction "VDDP1_A7") (pintype "bidirectional"))
      (node (ref "U320") (pin "B7") (pinfunction "VDDP2_B7") (pintype "bidirectional"))
      (node (ref "U320") (pin "C7") (pinfunction "VDDP3_C7") (pintype "bidirectional"))
      (node (ref "U320") (pin "E7") (pinfunction "VBST1_E7") (pintype "bidirectional"))
      (node (ref "U320") (pin "F7") (pinfunction "VBST2_F7") (pintype "bidirectional"))
      (node (ref "U320") (pin "G7") (pinfunction "VBST3_G7") (pintype "bidirectional"))
      (node (ref "VBST") (pin "TP") (pinfunction "PP_TP") (pintype "input"))
    )
    (net (code "90") (name "VBUS") (class "Default")
      (node (ref "P102") (pin "11") (pinfunction "11_11") (pintype "passive"))
    )
    (net (code "91") (name "VINB") (class "Default")
      (node (ref "L340") (pin "1") (pinfunction "1_1") (pintype "passive"))
      (node (ref "U320") (pin "E6") (pinfunction "VINB1_E6") (pintype "bidirectional"))
      (node (ref "U320") (pin "F6") (pinfunction "VINB2_F6") (pintype "bidirectional"))
      (node (ref "U320") (pin "G6") (pinfunction "VINB3_G6") (pintype "bidirectional"))
    )
    (net (code "92") (name "VSYS") (class "Default")
      (node (ref "P102") (pin "17") (pinfunction "17_17") (pintype "passive"))
    )
    (net (code "93") (name "unconnected-(EE_GND3-PP-PadTP)") (class "Default")
      (node (ref "EE_GND3") (pin "TP") (pinfunction "PP_TP") (pintype "input"))
    )
    (net (code "94") (name "unconnected-(EE_GND4-PP-PadTP)") (class "Default")
      (node (ref "EE_GND4") (pin "TP") (pinfunction "PP_TP") (pintype "input"))
    )
    (net (code "95") (name "unconnected-(EE_WP1-PP-PadTP)") (class "Default")
      (node (ref "EE_WP1") (pin "TP") (pinfunction "PP_TP") (pintype "input"))
    )
    (net (code "96") (name "unconnected-(U1-NC-Pad1)") (class "Default")
      (node (ref "U1") (pin "1") (pinfunction "NC_1") (pintype "bidirectional"))
    )
    (net (code "97") (name "unconnected-(U1-NC-Pad2)") (class "Default")
      (node (ref "U1") (pin "2") (pinfunction "NC_2") (pintype "bidirectional"))
    )
    (net (code "98") (name "unconnected-(U1-NC-Pad20)") (class "Default")
      (node (ref "U1") (pin "20") (pinfunction "NC_20") (pintype "bidirectional"))
    )
    (net (code "99") (name "unconnected-(U2-P4-Pad4)") (class "Default")
      (node (ref "U2") (pin "4") (pinfunction "P4_4") (pintype "bidirectional"))
    )
    (net (code "100") (name "unconnected-(U320-DATAI3-PadB3)") (class "Default")
      (node (ref "U320") (pin "B3") (pinfunction "DATAI3_B3") (pintype "bidirectional"))
    )
  )
)
